# msrgyro.net
KiCad netlist of a schematic drawn in EAGLE
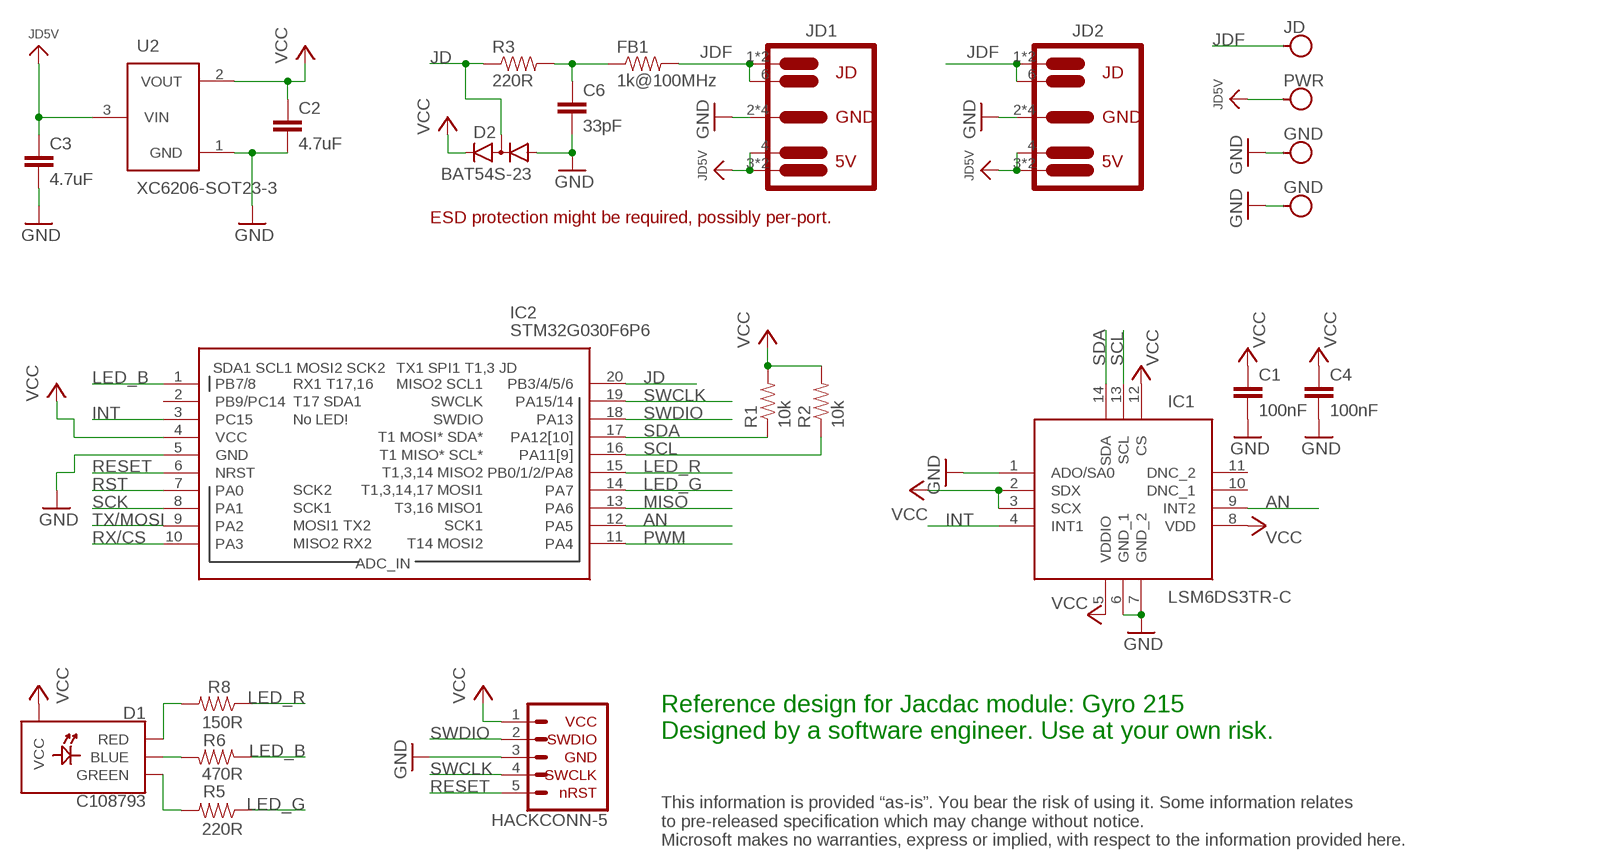
[diagram p0: schematic, sheet 1]

(export (version "E")
  (design (tool "Eeschema 10.0.6"))
  (components
    (comp (ref "C1")
      (value "100nF")
      (footprint "eagle-import:0402")
      (libsource (lib "eagle-import") (part "CAP_0402"))
    )
    (comp (ref "C2")
      (value "4.7uF")
      (footprint "eagle-import:0402")
      (libsource (lib "eagle-import") (part "CAP_0402"))
    )
    (comp (ref "C3")
      (value "4.7uF")
      (footprint "eagle-import:0402")
      (libsource (lib "eagle-import") (part "CAP_0402"))
    )
    (comp (ref "C4")
      (value "100nF")
      (footprint "eagle-import:0402")
      (libsource (lib "eagle-import") (part "CAP_0402"))
    )
    (comp (ref "C6")
      (value "33pF")
      (footprint "eagle-import:0402")
      (libsource (lib "eagle-import") (part "CAP_0402"))
    )
    (comp (ref "D1")
      (value "C108793")
      (footprint "eagle-import:LED-RGB-2020")
      (libsource (lib "eagle-import") (part "LED-RGB-CA-2020"))
    )
    (comp (ref "D2")
      (value "BAT54S-23")
      (footprint "eagle-import:SOT23-3")
      (libsource (lib "eagle-import") (part "BAT54S-23"))
    )
    (comp (ref "FB1")
      (value "1k@100MHz")
      (footprint "eagle-import:0402")
      (libsource (lib "eagle-import") (part "RES_0402"))
    )
    (comp (ref "IC1")
      (value "LSM6DS3TR-C")
      (footprint "eagle-import:LGA-14-2.5_3")
      (libsource (lib "eagle-import") (part "LSM6DS3TR-C"))
    )
    (comp (ref "IC2")
      (value "STM32G030F6P6")
      (footprint "eagle-import:SOP65P640X120-20N")
      (libsource (lib "eagle-import") (part "STM32G030F8P6"))
    )
    (comp (ref "J1")
      (value "JD")
      (footprint "eagle-import:M3-HOLE-DATA")
      (libsource (lib "eagle-import") (part "JACDAC-M3-DATA"))
    )
    (comp (ref "J2")
      (value "PWR")
      (footprint "eagle-import:M3-HOLE-PWR")
      (libsource (lib "eagle-import") (part "JACDAC-M3-PWR"))
    )
    (comp (ref "J3")
      (value "GND")
      (footprint "eagle-import:M3-HOLE-GND")
      (libsource (lib "eagle-import") (part "JACDAC-M3-GND"))
    )
    (comp (ref "J4")
      (value "GND")
      (footprint "eagle-import:M3-HOLE-GND")
      (libsource (lib "eagle-import") (part "JACDAC-M3-GND"))
    )
    (comp (ref "J6")
      (value "HACK-CONNECT-5")
      (footprint "eagle-import:HC5-22-62")
      (libsource (lib "eagle-import") (part "HACK-CONNECT-5"))
    )
    (comp (ref "JD1")
      (value "JACDAC-EDGE-OUTIE")
      (footprint "eagle-import:JD-EDGE-OUTIE")
      (libsource (lib "eagle-import") (part "JACDAC-EDGE-OUTIE"))
    )
    (comp (ref "JD2")
      (value "JACDAC-EDGE-OUTIE")
      (footprint "eagle-import:JD-EDGE-OUTIE")
      (libsource (lib "eagle-import") (part "JACDAC-EDGE-OUTIE"))
    )
    (comp (ref "R1")
      (value "10k")
      (footprint "eagle-import:0402")
      (libsource (lib "eagle-import") (part "RES_0402"))
    )
    (comp (ref "R2")
      (value "10k")
      (footprint "eagle-import:0402")
      (libsource (lib "eagle-import") (part "RES_0402"))
    )
    (comp (ref "R3")
      (value "220R")
      (footprint "eagle-import:0402")
      (libsource (lib "eagle-import") (part "RES_0402"))
    )
    (comp (ref "R5")
      (value "220R")
      (footprint "eagle-import:0402")
      (libsource (lib "eagle-import") (part "RES_0402"))
    )
    (comp (ref "R6")
      (value "470R")
      (footprint "eagle-import:0402")
      (libsource (lib "eagle-import") (part "RES_0402"))
    )
    (comp (ref "R8")
      (value "150R")
      (footprint "eagle-import:0402")
      (libsource (lib "eagle-import") (part "RES_0402"))
    )
    (comp (ref "U2")
      (value "XC6206-SOT23-3")
      (footprint "eagle-import:SOT23-3-W")
      (libsource (lib "eagle-import") (part "XC6206-SOT23-3"))
    )
  )
  (nets
    (net (code "1") (name "/AN") (class "Default")
      (node (ref "IC1") (pin "9") (pinfunction "INT2_9") (pintype "bidirectional"))
      (node (ref "IC2") (pin "12") (pinfunction "PA5_12") (pintype "bidirectional"))
    )
    (net (code "2") (name "/INT") (class "Default")
      (node (ref "IC1") (pin "4") (pinfunction "INT1_4") (pintype "bidirectional"))
      (node (ref "IC2") (pin "3") (pinfunction "PC15_3") (pintype "bidirectional"))
    )
    (net (code "3") (name "/JD") (class "Default")
      (node (ref "D2") (pin "3") (pinfunction "C1A2_3") (pintype "passive"))
      (node (ref "IC2") (pin "20") (pinfunction "PB3/4/5/6_20") (pintype "bidirectional"))
      (node (ref "R3") (pin "1") (pinfunction "1_1") (pintype "passive"))
    )
    (net (code "4") (name "/JDF") (class "Default")
      (node (ref "FB1") (pin "2") (pinfunction "2_2") (pintype "passive"))
      (node (ref "J1") (pin "H") (pinfunction "P$1_H") (pintype "bidirectional"))
      (node (ref "JD1") (pin "1") (pinfunction "2_1") (pintype "bidirectional"))
      (node (ref "JD1") (pin "6") (pinfunction "6_6") (pintype "bidirectional"))
      (node (ref "JD1") (pin "P$3") (pinfunction "2_P$3") (pintype "bidirectional"))
      (node (ref "JD2") (pin "1") (pinfunction "2_1") (pintype "bidirectional"))
      (node (ref "JD2") (pin "6") (pinfunction "6_6") (pintype "bidirectional"))
      (node (ref "JD2") (pin "P$3") (pinfunction "2_P$3") (pintype "bidirectional"))
    )
    (net (code "5") (name "/LED_B") (class "Default")
      (node (ref "IC2") (pin "1") (pinfunction "PB7/8_1") (pintype "input"))
      (node (ref "R6") (pin "1") (pinfunction "1_1") (pintype "passive"))
    )
    (net (code "6") (name "/LED_G") (class "Default")
      (node (ref "IC2") (pin "14") (pinfunction "PA7_14") (pintype "bidirectional"))
      (node (ref "R5") (pin "1") (pinfunction "1_1") (pintype "passive"))
    )
    (net (code "7") (name "/LED_R") (class "Default")
      (node (ref "IC2") (pin "15") (pinfunction "PB0/1/2/PA8_15") (pintype "input"))
      (node (ref "R8") (pin "1") (pinfunction "1_1") (pintype "passive"))
    )
    (net (code "8") (name "/MISO") (class "Default")
      (node (ref "IC2") (pin "13") (pinfunction "PA6_13") (pintype "bidirectional"))
    )
    (net (code "9") (name "/PWM") (class "Default")
      (node (ref "IC2") (pin "11") (pinfunction "PA4_11") (pintype "bidirectional"))
    )
    (net (code "10") (name "/RESET") (class "Default")
      (node (ref "IC2") (pin "6") (pinfunction "NRST_6") (pintype "bidirectional"))
      (node (ref "J6") (pin "5") (pinfunction "NRST_5") (pintype "bidirectional"))
    )
    (net (code "11") (name "/RST") (class "Default")
      (node (ref "IC2") (pin "7") (pinfunction "PA0_7") (pintype "bidirectional"))
    )
    (net (code "12") (name "/RX{slash}CS") (class "Default")
      (node (ref "IC2") (pin "10") (pinfunction "PA3_10") (pintype "bidirectional"))
    )
    (net (code "13") (name "/SCK") (class "Default")
      (node (ref "IC2") (pin "8") (pinfunction "PA1_8") (pintype "bidirectional"))
    )
    (net (code "14") (name "/SCL") (class "Default")
      (node (ref "IC1") (pin "13") (pinfunction "SCL_13") (pintype "bidirectional"))
      (node (ref "IC2") (pin "16") (pinfunction "PA11[9]_16") (pintype "input"))
      (node (ref "R2") (pin "1") (pinfunction "1_1") (pintype "passive"))
    )
    (net (code "15") (name "/SDA") (class "Default")
      (node (ref "IC1") (pin "14") (pinfunction "SDA_14") (pintype "bidirectional"))
      (node (ref "IC2") (pin "17") (pinfunction "PA12[10]_17") (pintype "bidirectional"))
      (node (ref "R1") (pin "1") (pinfunction "1_1") (pintype "passive"))
    )
    (net (code "16") (name "/SWCLK") (class "Default")
      (node (ref "IC2") (pin "19") (pinfunction "PA15/14_19") (pintype "bidirectional"))
      (node (ref "J6") (pin "4") (pinfunction "SWCLK_4") (pintype "input"))
    )
    (net (code "17") (name "/SWDIO") (class "Default")
      (node (ref "IC2") (pin "18") (pinfunction "PA13_18") (pintype "bidirectional"))
      (node (ref "J6") (pin "2") (pinfunction "SWDIO_2") (pintype "input"))
    )
    (net (code "18") (name "/TX{slash}MOSI") (class "Default")
      (node (ref "IC2") (pin "9") (pinfunction "PA2_9") (pintype "bidirectional"))
    )
    (net (code "19") (name "GND") (class "Default")
      (node (ref "C1") (pin "2") (pinfunction "2_2") (pintype "passive"))
      (node (ref "C2") (pin "2") (pinfunction "2_2") (pintype "passive"))
      (node (ref "C3") (pin "2") (pinfunction "2_2") (pintype "passive"))
      (node (ref "C4") (pin "2") (pinfunction "2_2") (pintype "passive"))
      (node (ref "C6") (pin "2") (pinfunction "2_2") (pintype "passive"))
      (node (ref "D2") (pin "1") (pinfunction "A1_1") (pintype "passive"))
      (node (ref "IC1") (pin "1") (pinfunction "ADO/SA0_1") (pintype "bidirectional"))
      (node (ref "IC1") (pin "6") (pinfunction "GND_1_6") (pintype "bidirectional"))
      (node (ref "IC1") (pin "7") (pinfunction "GND_2_7") (pintype "bidirectional"))
      (node (ref "IC2") (pin "5") (pinfunction "GND_5") (pintype "power_in"))
      (node (ref "J3") (pin "H") (pinfunction "P$1_H") (pintype "bidirectional"))
      (node (ref "J4") (pin "H") (pinfunction "P$1_H") (pintype "bidirectional"))
      (node (ref "J6") (pin "3") (pinfunction "GND_3") (pintype "power_in"))
      (node (ref "JD1") (pin "2") (pinfunction "1_2") (pintype "power_in"))
      (node (ref "JD1") (pin "5") (pinfunction "1_5") (pintype "power_in"))
      (node (ref "JD1") (pin "P$2") (pinfunction "1_P$2") (pintype "power_in"))
      (node (ref "JD1") (pin "P$4") (pinfunction "1_P$4") (pintype "power_in"))
      (node (ref "JD2") (pin "2") (pinfunction "1_2") (pintype "power_in"))
      (node (ref "JD2") (pin "5") (pinfunction "1_5") (pintype "power_in"))
      (node (ref "JD2") (pin "P$2") (pinfunction "1_P$2") (pintype "power_in"))
      (node (ref "JD2") (pin "P$4") (pinfunction "1_P$4") (pintype "power_in"))
      (node (ref "U2") (pin "1") (pinfunction "GND_1") (pintype "bidirectional"))
    )
    (net (code "20") (name "JD5V") (class "Default")
      (node (ref "C3") (pin "1") (pinfunction "1_1") (pintype "passive"))
      (node (ref "J2") (pin "H") (pinfunction "P$1_H") (pintype "bidirectional"))
      (node (ref "JD1") (pin "3") (pinfunction "3_3") (pintype "power_in"))
      (node (ref "JD1") (pin "4") (pinfunction "4_4") (pintype "power_in"))
      (node (ref "JD1") (pin "P$1") (pinfunction "3_P$1") (pintype "power_in"))
      (node (ref "JD2") (pin "3") (pinfunction "3_3") (pintype "power_in"))
      (node (ref "JD2") (pin "4") (pinfunction "4_4") (pintype "power_in"))
      (node (ref "JD2") (pin "P$1") (pinfunction "3_P$1") (pintype "power_in"))
      (node (ref "U2") (pin "3") (pinfunction "VIN_3") (pintype "bidirectional"))
    )
    (net (code "21") (name "Net-(C6-Pad1)") (class "Default")
      (node (ref "C6") (pin "1") (pinfunction "1_1") (pintype "passive"))
      (node (ref "FB1") (pin "1") (pinfunction "1_1") (pintype "passive"))
      (node (ref "R3") (pin "2") (pinfunction "2_2") (pintype "passive"))
    )
    (net (code "22") (name "Net-(D1-BLUE)") (class "Default")
      (node (ref "D1") (pin "B-") (pinfunction "BLUE_B-") (pintype "bidirectional"))
      (node (ref "R6") (pin "2") (pinfunction "2_2") (pintype "passive"))
    )
    (net (code "23") (name "Net-(D1-GREEN)") (class "Default")
      (node (ref "D1") (pin "G-") (pinfunction "GREEN_G-") (pintype "bidirectional"))
      (node (ref "R5") (pin "2") (pinfunction "2_2") (pintype "passive"))
    )
    (net (code "24") (name "Net-(D1-RED)") (class "Default")
      (node (ref "D1") (pin "R-") (pinfunction "RED_R-") (pintype "bidirectional"))
      (node (ref "R8") (pin "2") (pinfunction "2_2") (pintype "passive"))
    )
    (net (code "25") (name "VCC") (class "Default")
      (node (ref "C1") (pin "1") (pinfunction "1_1") (pintype "passive"))
      (node (ref "C2") (pin "1") (pinfunction "1_1") (pintype "passive"))
      (node (ref "C4") (pin "1") (pinfunction "1_1") (pintype "passive"))
      (node (ref "D1") (pin "PLUS") (pinfunction "VCC_PLUS") (pintype "bidirectional"))
      (node (ref "D2") (pin "2") (pinfunction "C2_2") (pintype "passive"))
      (node (ref "IC1") (pin "12") (pinfunction "CS_12") (pintype "bidirectional"))
      (node (ref "IC1") (pin "2") (pinfunction "SDX_2") (pintype "bidirectional"))
      (node (ref "IC1") (pin "3") (pinfunction "SCX_3") (pintype "bidirectional"))
      (node (ref "IC1") (pin "5") (pinfunction "VDDIO_5") (pintype "bidirectional"))
      (node (ref "IC1") (pin "8") (pinfunction "VDD_8") (pintype "bidirectional"))
      (node (ref "IC2") (pin "4") (pinfunction "VCC_4") (pintype "power_in"))
      (node (ref "J6") (pin "1") (pinfunction "VCC_1") (pintype "passive"))
      (node (ref "R1") (pin "2") (pinfunction "2_2") (pintype "passive"))
      (node (ref "R2") (pin "2") (pinfunction "2_2") (pintype "passive"))
      (node (ref "U2") (pin "2") (pinfunction "VOUT_2") (pintype "bidirectional"))
    )
    (net (code "26") (name "unconnected-(IC1-DNC_1-Pad10)") (class "Default")
      (node (ref "IC1") (pin "10") (pinfunction "DNC_1_10") (pintype "bidirectional"))
    )
    (net (code "27") (name "unconnected-(IC1-DNC_2-Pad11)") (class "Default")
      (node (ref "IC1") (pin "11") (pinfunction "DNC_2_11") (pintype "bidirectional"))
    )
    (net (code "28") (name "unconnected-(IC2-PB9{slash}PC14-Pad2)") (class "Default")
      (node (ref "IC2") (pin "2") (pinfunction "PB9/PC14_2") (pintype "bidirectional"))
    )
  )
)
